# Sheet1.net
KiCad netlist of a schematic drawn in Altium Designer
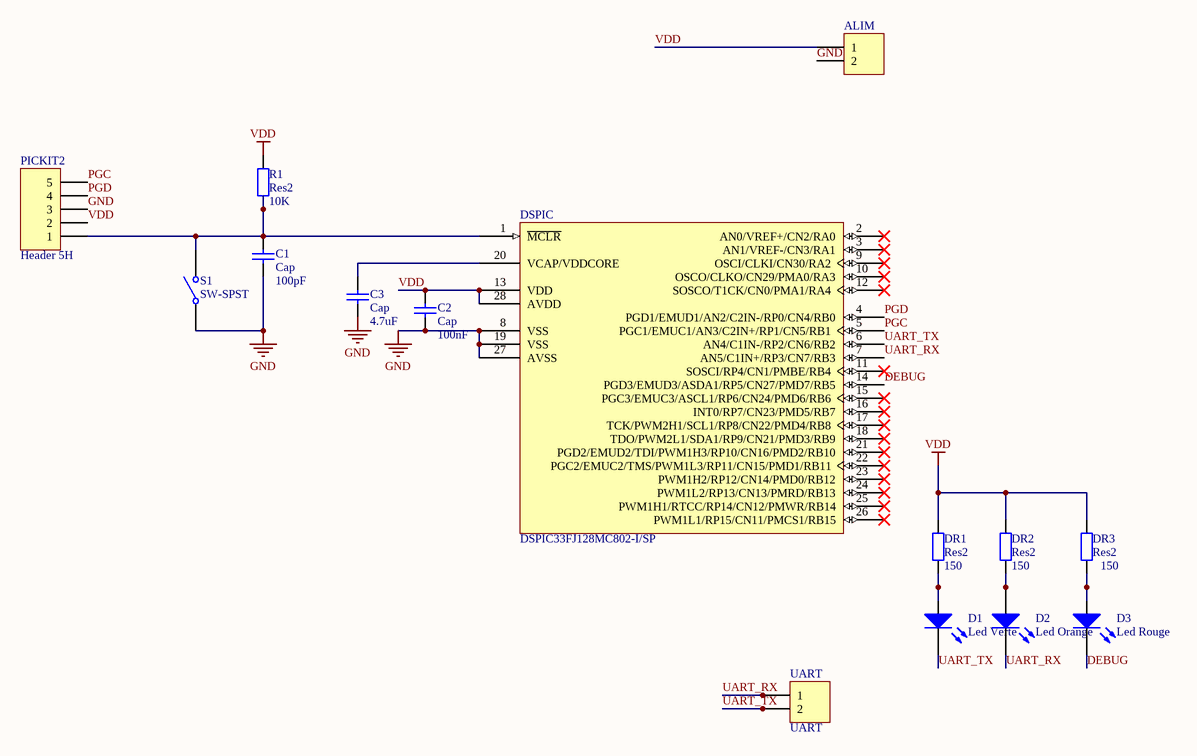
[diagram p0: Sheet1.SchDoc]

(export (version "E")
  (design (tool "Eeschema 10.0.6"))
  (components
    (comp (ref "ALIM")
      (value "Bornier_2")
      (footprint "Bornier_2")
      (description "Header, 2-Pin")
      (fields (field (name "PUBLISHER") "Altium Limited"))
      (libsource (lib "INTEGRATED_LIBRARY1_CONNECTEURS") (part "Bornier_2"))
    )
    (comp (ref "C1")
      (value "Cap")
      (footprint "RAD-0.3")
      (description "Capacitor")
      (fields (field (name "ALTIUM_VALUE") "100pF") (field (name "PUBLISHER") "Altium Limited"))
      (libsource (lib "Miscellaneous Devices") (part "Cap"))
    )
    (comp (ref "C2")
      (value "Cap")
      (footprint "RAD-0.3")
      (description "Capacitor")
      (fields (field (name "ALTIUM_VALUE") "100nF") (field (name "PUBLISHER") "Altium Limited"))
      (libsource (lib "Miscellaneous Devices") (part "Cap"))
    )
    (comp (ref "C3")
      (value "Cap")
      (footprint "RAD-0.3")
      (description "Capacitor")
      (fields (field (name "ALTIUM_VALUE") "4.7uF") (field (name "PUBLISHER") "Altium Limited"))
      (libsource (lib "Miscellaneous Devices") (part "Cap"))
    )
    (comp (ref "D1")
      (value "Led Verte")
      (footprint "LED")
      (description "LED")
      (fields (field (name "PUBLISHER") "Altium Limited"))
      (libsource (lib "LIBRAIRIE_INTEGREE_PHELMA1") (part "Led"))
    )
    (comp (ref "D2")
      (value "Led Orange")
      (footprint "LED")
      (description "LED")
      (fields (field (name "PUBLISHER") "Altium Limited"))
      (libsource (lib "LIBRAIRIE_INTEGREE_PHELMA1") (part "Led"))
    )
    (comp (ref "D3")
      (value "Led Rouge")
      (footprint "LED")
      (description "LED")
      (fields (field (name "PUBLISHER") "Altium Limited"))
      (libsource (lib "LIBRAIRIE_INTEGREE_PHELMA1") (part "Led"))
    )
    (comp (ref "DR1")
      (value "Res2")
      (footprint "AXIAL-0.4")
      (description "Resistor")
      (fields (field (name "ALTIUM_VALUE") "150") (field (name "PUBLISHER") "Altium Limited"))
      (libsource (lib "Miscellaneous Devices") (part "Res2"))
    )
    (comp (ref "DR2")
      (value "Res2")
      (footprint "AXIAL-0.4")
      (description "Resistor")
      (fields (field (name "ALTIUM_VALUE") "150") (field (name "PUBLISHER") "Altium Limited"))
      (libsource (lib "Miscellaneous Devices") (part "Res2"))
    )
    (comp (ref "DR3")
      (value "Res2")
      (footprint "AXIAL-0.4")
      (description "Resistor")
      (fields (field (name "ALTIUM_VALUE") "150") (field (name "PUBLISHER") "Altium Limited"))
      (libsource (lib "Miscellaneous Devices") (part "Res2"))
    )
    (comp (ref "DSPIC")
      (value "DSPIC33FJ128MC802-I/SP")
      (footprint "SPDIP300-SP28")
      (fields (field (name "PUBLISHER") "Altium Limited"))
      (libsource (lib "Microchip DSC 16-Bit dsPIC33F") (part "DSPIC33FJ128MC802-I/SP"))
    )
    (comp (ref "PICKIT2")
      (value "Header 5H")
      (footprint "HDR1X5")
      (description "Header, 5-Pin, Right Angle")
      (fields (field (name "PUBLISHER") "Altium Limited"))
      (libsource (lib "Miscellaneous Connectors") (part "Header 5H"))
    )
    (comp (ref "R1")
      (value "Res2")
      (footprint "AXIAL-0.4")
      (description "Resistor")
      (fields (field (name "ALTIUM_VALUE") "10K") (field (name "PUBLISHER") "Altium Limited"))
      (libsource (lib "Miscellaneous Devices") (part "Res2"))
    )
    (comp (ref "S1")
      (value "SW-SPST")
      (footprint "SPST-2")
      (description "Single-Pole, Single-Throw Switch")
      (fields (field (name "PUBLISHER") "Altium Limited"))
      (libsource (lib "Miscellaneous Devices") (part "SW-SPST"))
    )
    (comp (ref "UART")
      (value "UART")
      (footprint "Bornier_2")
      (description "Header, 2-Pin")
      (fields (field (name "PUBLISHER") "Altium Limited"))
      (libsource (lib "INTEGRATED_LIBRARY1_CONNECTEURS") (part "Bornier_2"))
    )
  )
  (nets
    (net (code "1") (name "/DEBUG") (class "Default")
      (node (ref "D3") (pin "2") (pinfunction "K_2") (pintype "passive"))
      (node (ref "DSPIC") (pin "14") (pinfunction "PGD3/EMUD3/ASDA1/RP5/CN27/PMD7/RB5_14") (pintype "bidirectional"))
    )
    (net (code "2") (name "/PGC") (class "Default")
      (node (ref "DSPIC") (pin "5") (pinfunction "PGC1/EMUC1/AN3/C2IN+/RP1/CN5/RB1_5") (pintype "bidirectional"))
      (node (ref "PICKIT2") (pin "5") (pinfunction "5_5") (pintype "passive"))
    )
    (net (code "3") (name "/PGD") (class "Default")
      (node (ref "DSPIC") (pin "4") (pinfunction "PGD1/EMUD1/AN2/C2IN-/RP0/CN4/RB0_4") (pintype "bidirectional"))
      (node (ref "PICKIT2") (pin "4") (pinfunction "4_4") (pintype "passive"))
    )
    (net (code "4") (name "/UART_RX") (class "Default")
      (node (ref "D2") (pin "2") (pinfunction "K_2") (pintype "passive"))
      (node (ref "DSPIC") (pin "7") (pinfunction "AN5/C1IN+/RP3/CN7/RB3_7") (pintype "bidirectional"))
      (node (ref "UART") (pin "1") (pinfunction "1_1") (pintype "passive"))
    )
    (net (code "5") (name "/UART_TX") (class "Default")
      (node (ref "D1") (pin "2") (pinfunction "K_2") (pintype "passive"))
      (node (ref "DSPIC") (pin "6") (pinfunction "AN4/C1IN-/RP2/CN6/RB2_6") (pintype "bidirectional"))
      (node (ref "UART") (pin "2") (pinfunction "2_2") (pintype "passive"))
    )
    (net (code "6") (name "GND") (class "Default")
      (node (ref "ALIM") (pin "2") (pinfunction "2_2") (pintype "passive"))
      (node (ref "C1") (pin "1") (pinfunction "1_1") (pintype "passive"))
      (node (ref "C2") (pin "1") (pinfunction "1_1") (pintype "passive"))
      (node (ref "C3") (pin "1") (pinfunction "1_1") (pintype "passive"))
      (node (ref "DSPIC") (pin "19") (pinfunction "VSS_19") (pintype "power_in"))
      (node (ref "DSPIC") (pin "27") (pinfunction "AVSS_27") (pintype "power_in"))
      (node (ref "DSPIC") (pin "8") (pinfunction "VSS_8") (pintype "power_in"))
      (node (ref "PICKIT2") (pin "3") (pinfunction "3_3") (pintype "passive"))
      (node (ref "S1") (pin "1") (pinfunction "COMMON_1") (pintype "passive"))
    )
    (net (code "7") (name "Net-(D1-A)") (class "Default")
      (node (ref "D1") (pin "1") (pinfunction "A_1") (pintype "passive"))
      (node (ref "DR1") (pin "1") (pinfunction "1_1") (pintype "passive"))
    )
    (net (code "8") (name "Net-(D2-A)") (class "Default")
      (node (ref "D2") (pin "1") (pinfunction "A_1") (pintype "passive"))
      (node (ref "DR2") (pin "1") (pinfunction "1_1") (pintype "passive"))
    )
    (net (code "9") (name "Net-(D3-A)") (class "Default")
      (node (ref "D3") (pin "1") (pinfunction "A_1") (pintype "passive"))
      (node (ref "DR3") (pin "1") (pinfunction "1_1") (pintype "passive"))
    )
    (net (code "10") (name "Net-(DSPIC-VCAP{slash}VDDCORE)") (class "Default")
      (node (ref "C3") (pin "2") (pinfunction "2_2") (pintype "passive"))
      (node (ref "DSPIC") (pin "20") (pinfunction "VCAP/VDDCORE_20") (pintype "power_in"))
    )
    (net (code "11") (name "Net-(DSPIC-~{MCLR})") (class "Default")
      (node (ref "C1") (pin "2") (pinfunction "2_2") (pintype "passive"))
      (node (ref "DSPIC") (pin "1") (pinfunction "~{MCLR}_1") (pintype "input"))
      (node (ref "PICKIT2") (pin "1") (pinfunction "1_1") (pintype "passive"))
      (node (ref "R1") (pin "1") (pinfunction "1_1") (pintype "passive"))
      (node (ref "S1") (pin "2") (pinfunction "NO_2") (pintype "passive"))
    )
    (net (code "12") (name "VDD") (class "Default")
      (node (ref "ALIM") (pin "1") (pinfunction "1_1") (pintype "passive"))
      (node (ref "C2") (pin "2") (pinfunction "2_2") (pintype "passive"))
      (node (ref "DR1") (pin "2") (pinfunction "2_2") (pintype "passive"))
      (node (ref "DR2") (pin "2") (pinfunction "2_2") (pintype "passive"))
      (node (ref "DR3") (pin "2") (pinfunction "2_2") (pintype "passive"))
      (node (ref "DSPIC") (pin "13") (pinfunction "VDD_13") (pintype "power_in"))
      (node (ref "DSPIC") (pin "28") (pinfunction "AVDD_28") (pintype "power_in"))
      (node (ref "PICKIT2") (pin "2") (pinfunction "2_2") (pintype "passive"))
      (node (ref "R1") (pin "2") (pinfunction "2_2") (pintype "passive"))
    )
    (net (code "13") (name "unconnected-(DSPIC-AN0{slash}VREF+{slash}CN2{slash}RA0-Pad2)") (class "Default")
      (node (ref "DSPIC") (pin "2") (pinfunction "AN0/VREF+/CN2/RA0_2") (pintype "bidirectional+no_connect"))
    )
    (net (code "14") (name "unconnected-(DSPIC-AN1{slash}VREF-{slash}CN3{slash}RA1-Pad3)") (class "Default")
      (node (ref "DSPIC") (pin "3") (pinfunction "AN1/VREF-/CN3/RA1_3") (pintype "bidirectional+no_connect"))
    )
    (net (code "15") (name "unconnected-(DSPIC-INT0{slash}RP7{slash}CN23{slash}PMD5{slash}RB7-Pad16)") (class "Default")
      (node (ref "DSPIC") (pin "16") (pinfunction "INT0/RP7/CN23/PMD5/RB7_16") (pintype "bidirectional+no_connect"))
    )
    (net (code "16") (name "unconnected-(DSPIC-OSCI{slash}CLKI{slash}CN30{slash}RA2-Pad9)") (class "Default")
      (node (ref "DSPIC") (pin "9") (pinfunction "OSCI/CLKI/CN30/RA2_9") (pintype "bidirectional+no_connect"))
    )
    (net (code "17") (name "unconnected-(DSPIC-OSCO{slash}CLKO{slash}CN29{slash}PMA0{slash}RA3-Pad10)") (class "Default")
      (node (ref "DSPIC") (pin "10") (pinfunction "OSCO/CLKO/CN29/PMA0/RA3_10") (pintype "bidirectional+no_connect"))
    )
    (net (code "18") (name "unconnected-(DSPIC-PGC2{slash}EMUC2{slash}TMS{slash}PWM1L3{slash}RP11{slash}CN15{slash}PMD1{slash}RB11-Pad22)") (class "Default")
      (node (ref "DSPIC") (pin "22") (pinfunction "PGC2/EMUC2/TMS/PWM1L3/RP11/CN15/PMD1/RB11_22") (pintype "bidirectional+no_connect"))
    )
    (net (code "19") (name "unconnected-(DSPIC-PGC3{slash}EMUC3{slash}ASCL1{slash}RP6{slash}CN24{slash}PMD6{slash}RB6-Pad15)") (class "Default")
      (node (ref "DSPIC") (pin "15") (pinfunction "PGC3/EMUC3/ASCL1/RP6/CN24/PMD6/RB6_15") (pintype "bidirectional+no_connect"))
    )
    (net (code "20") (name "unconnected-(DSPIC-PGD2{slash}EMUD2{slash}TDI{slash}PWM1H3{slash}RP10{slash}CN16{slash}PMD2{slash}RB10-Pad21)") (class "Default")
      (node (ref "DSPIC") (pin "21") (pinfunction "PGD2/EMUD2/TDI/PWM1H3/RP10/CN16/PMD2/RB10_21") (pintype "bidirectional+no_connect"))
    )
    (net (code "21") (name "unconnected-(DSPIC-PWM1H1{slash}RTCC{slash}RP14{slash}CN12{slash}PMWR{slash}RB14-Pad25)") (class "Default")
      (node (ref "DSPIC") (pin "25") (pinfunction "PWM1H1/RTCC/RP14/CN12/PMWR/RB14_25") (pintype "bidirectional+no_connect"))
    )
    (net (code "22") (name "unconnected-(DSPIC-PWM1H2{slash}RP12{slash}CN14{slash}PMD0{slash}RB12-Pad23)") (class "Default")
      (node (ref "DSPIC") (pin "23") (pinfunction "PWM1H2/RP12/CN14/PMD0/RB12_23") (pintype "bidirectional+no_connect"))
    )
    (net (code "23") (name "unconnected-(DSPIC-PWM1L1{slash}RP15{slash}CN11{slash}PMCS1{slash}RB15-Pad26)") (class "Default")
      (node (ref "DSPIC") (pin "26") (pinfunction "PWM1L1/RP15/CN11/PMCS1/RB15_26") (pintype "bidirectional+no_connect"))
    )
    (net (code "24") (name "unconnected-(DSPIC-PWM1L2{slash}RP13{slash}CN13{slash}PMRD{slash}RB13-Pad24)") (class "Default")
      (node (ref "DSPIC") (pin "24") (pinfunction "PWM1L2/RP13/CN13/PMRD/RB13_24") (pintype "bidirectional+no_connect"))
    )
    (net (code "25") (name "unconnected-(DSPIC-SOSCI{slash}RP4{slash}CN1{slash}PMBE{slash}RB4-Pad11)") (class "Default")
      (node (ref "DSPIC") (pin "11") (pinfunction "SOSCI/RP4/CN1/PMBE/RB4_11") (pintype "bidirectional+no_connect"))
    )
    (net (code "26") (name "unconnected-(DSPIC-SOSCO{slash}T1CK{slash}CN0{slash}PMA1{slash}RA4-Pad12)") (class "Default")
      (node (ref "DSPIC") (pin "12") (pinfunction "SOSCO/T1CK/CN0/PMA1/RA4_12") (pintype "bidirectional+no_connect"))
    )
    (net (code "27") (name "unconnected-(DSPIC-TCK{slash}PWM2H1{slash}SCL1{slash}RP8{slash}CN22{slash}PMD4{slash}RB8-Pad17)") (class "Default")
      (node (ref "DSPIC") (pin "17") (pinfunction "TCK/PWM2H1/SCL1/RP8/CN22/PMD4/RB8_17") (pintype "bidirectional+no_connect"))
    )
    (net (code "28") (name "unconnected-(DSPIC-TDO{slash}PWM2L1{slash}SDA1{slash}RP9{slash}CN21{slash}PMD3{slash}RB9-Pad18)") (class "Default")
      (node (ref "DSPIC") (pin "18") (pinfunction "TDO/PWM2L1/SDA1/RP9/CN21/PMD3/RB9_18") (pintype "bidirectional+no_connect"))
    )
  )
)
